# Schematic_transporter.net
KiCad netlist of a schematic drawn in EAGLE
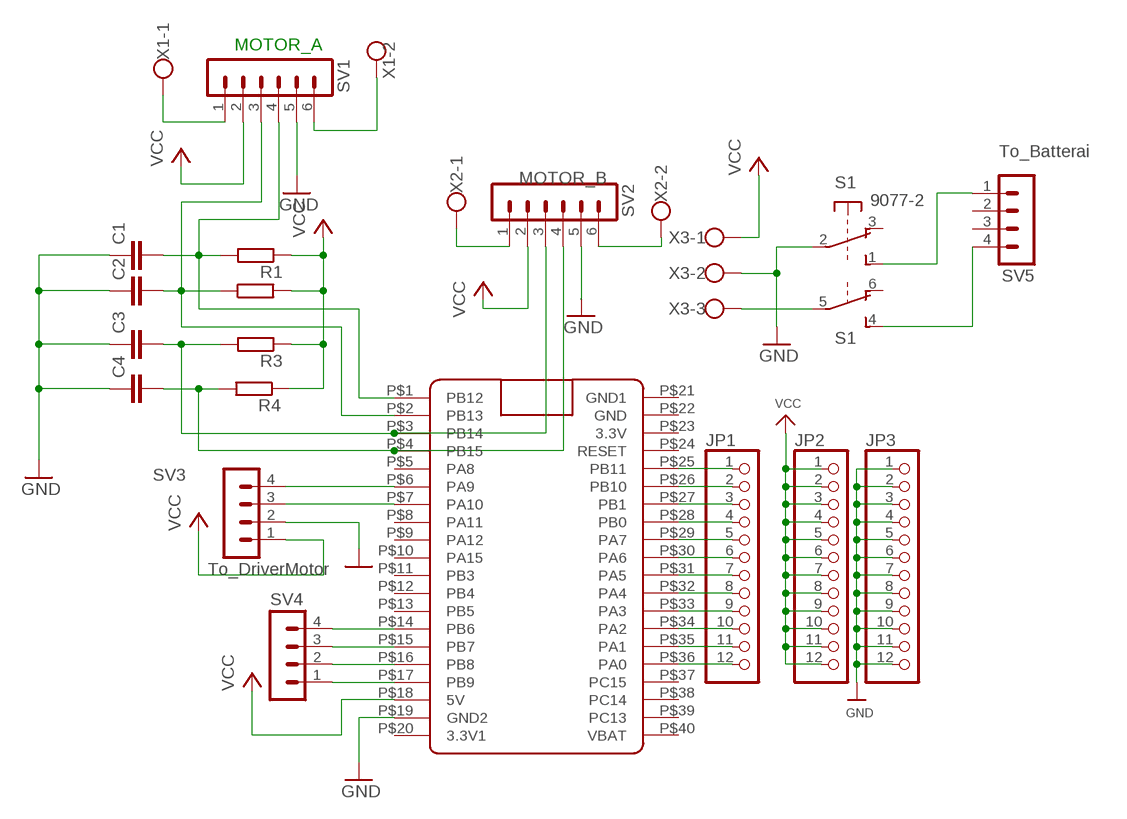
[diagram p0: schematic, sheet 1]

(export (version "E")
  (design (tool "Eeschema 10.0.6"))
  (components
    (comp (ref "C1")
      (value "C-EU050-024X044")
      (footprint "eagle-import:C050-024X044")
      (libsource (lib "eagle-import") (part "C-EU050-024X044"))
    )
    (comp (ref "C2")
      (value "C-EU050-024X044")
      (footprint "eagle-import:C050-024X044")
      (libsource (lib "eagle-import") (part "C-EU050-024X044"))
    )
    (comp (ref "C3")
      (value "C-EU050-024X044")
      (footprint "eagle-import:C050-024X044")
      (libsource (lib "eagle-import") (part "C-EU050-024X044"))
    )
    (comp (ref "C4")
      (value "C-EU050-024X044")
      (footprint "eagle-import:C050-024X044")
      (libsource (lib "eagle-import") (part "C-EU050-024X044"))
    )
    (comp (ref "JP1")
      (value "PINHD-1X12")
      (footprint "eagle-import:1X12")
      (libsource (lib "eagle-import") (part "PINHD-1X12"))
    )
    (comp (ref "JP2")
      (value "PINHD-1X12")
      (footprint "eagle-import:1X12")
      (libsource (lib "eagle-import") (part "PINHD-1X12"))
    )
    (comp (ref "JP3")
      (value "PINHD-1X12")
      (footprint "eagle-import:1X12")
      (libsource (lib "eagle-import") (part "PINHD-1X12"))
    )
    (comp (ref "R1")
      (value "R-EU_0207/7")
      (footprint "eagle-import:0207_7")
      (libsource (lib "eagle-import") (part "R-EU_0207/7"))
    )
    (comp (ref "R2")
      (value "R-EU_0207/7")
      (footprint "eagle-import:0207_7")
      (libsource (lib "eagle-import") (part "R-EU_0207/7"))
    )
    (comp (ref "R3")
      (value "R-EU_0207/7")
      (footprint "eagle-import:0207_7")
      (libsource (lib "eagle-import") (part "R-EU_0207/7"))
    )
    (comp (ref "R4")
      (value "R-EU_0207/7")
      (footprint "eagle-import:0207_7")
      (libsource (lib "eagle-import") (part "R-EU_0207/7"))
    )
    (comp (ref "S1")
      (value "9077-2")
      (footprint "eagle-import:9077-2")
      (libsource (lib "eagle-import") (part "9077-2"))
    )
    (comp (ref "SV1")
      (value "MA06-1")
      (footprint "eagle-import:MA06-1")
      (libsource (lib "eagle-import") (part "MA06-1"))
    )
    (comp (ref "SV2")
      (value "MA06-1")
      (footprint "eagle-import:MA06-1")
      (libsource (lib "eagle-import") (part "MA06-1"))
    )
    (comp (ref "SV3")
      (value "MA04-1")
      (footprint "eagle-import:MA04-1")
      (libsource (lib "eagle-import") (part "MA04-1"))
    )
    (comp (ref "SV4")
      (value "MA04-1")
      (footprint "eagle-import:MA04-1")
      (libsource (lib "eagle-import") (part "MA04-1"))
    )
    (comp (ref "SV5")
      (value "MA04-1")
      (footprint "eagle-import:MA04-1")
      (libsource (lib "eagle-import") (part "MA04-1"))
    )
    (comp (ref "U$1")
      (value "BLUE_PILL")
      (footprint "eagle-import:BLUE_PILL")
      (libsource (lib "eagle-import") (part "BLUE_PILL"))
    )
    (comp (ref "X1")
      (value "W237-102")
      (footprint "eagle-import:W237-102")
      (fields (field (name "MPN") "237-102"))
      (libsource (lib "eagle-import") (part "W237-102"))
    )
    (comp (ref "X2")
      (value "W237-102")
      (footprint "eagle-import:W237-102")
      (fields (field (name "MPN") "237-102"))
      (libsource (lib "eagle-import") (part "W237-102"))
    )
    (comp (ref "X3")
      (value "W237-103")
      (footprint "eagle-import:W237-103")
      (fields (field (name "MPN") "237-103"))
      (libsource (lib "eagle-import") (part "W237-103"))
    )
  )
  (nets
    (net (code "1") (name "/GND1") (class "Default")
      (node (ref "U$1") (pin "P$21") (pinfunction "GND1_P$21") (pintype "power_in"))
    )
    (net (code "2") (name "GND") (class "Default")
      (node (ref "C1") (pin "1") (pinfunction "1_1") (pintype "passive"))
      (node (ref "C2") (pin "1") (pinfunction "1_1") (pintype "passive"))
      (node (ref "C3") (pin "1") (pinfunction "1_1") (pintype "passive"))
      (node (ref "C4") (pin "1") (pinfunction "1_1") (pintype "passive"))
      (node (ref "JP3") (pin "1") (pinfunction "1_1") (pintype "passive"))
      (node (ref "JP3") (pin "10") (pinfunction "10_10") (pintype "passive"))
      (node (ref "JP3") (pin "11") (pinfunction "11_11") (pintype "passive"))
      (node (ref "JP3") (pin "12") (pinfunction "12_12") (pintype "passive"))
      (node (ref "JP3") (pin "2") (pinfunction "2_2") (pintype "passive"))
      (node (ref "JP3") (pin "3") (pinfunction "3_3") (pintype "passive"))
      (node (ref "JP3") (pin "4") (pinfunction "4_4") (pintype "passive"))
      (node (ref "JP3") (pin "5") (pinfunction "5_5") (pintype "passive"))
      (node (ref "JP3") (pin "6") (pinfunction "6_6") (pintype "passive"))
      (node (ref "JP3") (pin "7") (pinfunction "7_7") (pintype "passive"))
      (node (ref "JP3") (pin "8") (pinfunction "8_8") (pintype "passive"))
      (node (ref "JP3") (pin "9") (pinfunction "9_9") (pintype "passive"))
      (node (ref "S1") (pin "2") (pinfunction "P_2") (pintype "passive"))
      (node (ref "SV1") (pin "5") (pinfunction "5_5") (pintype "passive"))
      (node (ref "SV2") (pin "5") (pinfunction "5_5") (pintype "passive"))
      (node (ref "SV3") (pin "2") (pinfunction "2_2") (pintype "passive"))
      (node (ref "U$1") (pin "P$19") (pinfunction "GND2_P$19") (pintype "bidirectional"))
      (node (ref "X3") (pin "2") (pinfunction "KL_2") (pintype "passive"))
    )
    (net (code "3") (name "Net-(S1A-S)") (class "Default")
      (node (ref "S1") (pin "1") (pinfunction "S_1") (pintype "passive"))
      (node (ref "SV5") (pin "1") (pinfunction "1_1") (pintype "passive"))
    )
    (net (code "4") (name "Net-(S1B-P)") (class "Default")
      (node (ref "S1") (pin "5") (pinfunction "P_5") (pintype "passive"))
      (node (ref "X3") (pin "3") (pinfunction "KL_3") (pintype "passive"))
    )
    (net (code "5") (name "Net-(S1B-S)") (class "Default")
      (node (ref "S1") (pin "4") (pinfunction "S_4") (pintype "passive"))
      (node (ref "SV5") (pin "4") (pinfunction "4_4") (pintype "passive"))
    )
    (net (code "6") (name "Net-(U$1-PA0)") (class "Default")
      (node (ref "JP1") (pin "12") (pinfunction "12_12") (pintype "passive"))
      (node (ref "U$1") (pin "P$36") (pinfunction "PA0_P$36") (pintype "bidirectional"))
    )
    (net (code "7") (name "Net-(U$1-PA1)") (class "Default")
      (node (ref "JP1") (pin "11") (pinfunction "11_11") (pintype "passive"))
      (node (ref "U$1") (pin "P$35") (pinfunction "PA1_P$35") (pintype "bidirectional"))
    )
    (net (code "8") (name "Net-(U$1-PA2)") (class "Default")
      (node (ref "JP1") (pin "10") (pinfunction "10_10") (pintype "passive"))
      (node (ref "U$1") (pin "P$34") (pinfunction "PA2_P$34") (pintype "bidirectional"))
    )
    (net (code "9") (name "Net-(U$1-PA3)") (class "Default")
      (node (ref "JP1") (pin "9") (pinfunction "9_9") (pintype "passive"))
      (node (ref "U$1") (pin "P$33") (pinfunction "PA3_P$33") (pintype "bidirectional"))
    )
    (net (code "10") (name "Net-(U$1-PA4)") (class "Default")
      (node (ref "JP1") (pin "8") (pinfunction "8_8") (pintype "passive"))
      (node (ref "U$1") (pin "P$32") (pinfunction "PA4_P$32") (pintype "bidirectional"))
    )
    (net (code "11") (name "Net-(U$1-PA5)") (class "Default")
      (node (ref "JP1") (pin "7") (pinfunction "7_7") (pintype "passive"))
      (node (ref "U$1") (pin "P$31") (pinfunction "PA5_P$31") (pintype "bidirectional"))
    )
    (net (code "12") (name "Net-(U$1-PA6)") (class "Default")
      (node (ref "JP1") (pin "6") (pinfunction "6_6") (pintype "passive"))
      (node (ref "U$1") (pin "P$30") (pinfunction "PA6_P$30") (pintype "bidirectional"))
    )
    (net (code "13") (name "Net-(U$1-PA7)") (class "Default")
      (node (ref "JP1") (pin "5") (pinfunction "5_5") (pintype "passive"))
      (node (ref "U$1") (pin "P$29") (pinfunction "PA7_P$29") (pintype "bidirectional"))
    )
    (net (code "14") (name "Net-(U$1-PA9)") (class "Default")
      (node (ref "SV3") (pin "4") (pinfunction "4_4") (pintype "passive"))
      (node (ref "U$1") (pin "P$6") (pinfunction "PA9_P$6") (pintype "bidirectional"))
    )
    (net (code "15") (name "Net-(U$1-PA10)") (class "Default")
      (node (ref "SV3") (pin "3") (pinfunction "3_3") (pintype "passive"))
      (node (ref "U$1") (pin "P$7") (pinfunction "PA10_P$7") (pintype "bidirectional"))
    )
    (net (code "16") (name "Net-(U$1-PB0)") (class "Default")
      (node (ref "JP1") (pin "4") (pinfunction "4_4") (pintype "passive"))
      (node (ref "U$1") (pin "P$28") (pinfunction "PB0_P$28") (pintype "bidirectional"))
    )
    (net (code "17") (name "Net-(U$1-PB1)") (class "Default")
      (node (ref "JP1") (pin "3") (pinfunction "3_3") (pintype "passive"))
      (node (ref "U$1") (pin "P$27") (pinfunction "PB1_P$27") (pintype "bidirectional"))
    )
    (net (code "18") (name "Net-(U$1-PB6)") (class "Default")
      (node (ref "SV4") (pin "4") (pinfunction "4_4") (pintype "passive"))
      (node (ref "U$1") (pin "P$14") (pinfunction "PB6_P$14") (pintype "bidirectional"))
    )
    (net (code "19") (name "Net-(U$1-PB7)") (class "Default")
      (node (ref "SV4") (pin "3") (pinfunction "3_3") (pintype "passive"))
      (node (ref "U$1") (pin "P$15") (pinfunction "PB7_P$15") (pintype "bidirectional"))
    )
    (net (code "20") (name "Net-(U$1-PB8)") (class "Default")
      (node (ref "SV4") (pin "2") (pinfunction "2_2") (pintype "passive"))
      (node (ref "U$1") (pin "P$16") (pinfunction "PB8_P$16") (pintype "bidirectional"))
    )
    (net (code "21") (name "Net-(U$1-PB9)") (class "Default")
      (node (ref "SV4") (pin "1") (pinfunction "1_1") (pintype "passive"))
      (node (ref "U$1") (pin "P$17") (pinfunction "PB9_P$17") (pintype "bidirectional"))
    )
    (net (code "22") (name "Net-(U$1-PB10)") (class "Default")
      (node (ref "JP1") (pin "2") (pinfunction "2_2") (pintype "passive"))
      (node (ref "U$1") (pin "P$26") (pinfunction "PB10_P$26") (pintype "bidirectional"))
    )
    (net (code "23") (name "Net-(U$1-PB11)") (class "Default")
      (node (ref "JP1") (pin "1") (pinfunction "1_1") (pintype "passive"))
      (node (ref "U$1") (pin "P$25") (pinfunction "PB11_P$25") (pintype "bidirectional"))
    )
    (net (code "24") (name "Net-(U$1-PB12)") (class "Default")
      (node (ref "C1") (pin "2") (pinfunction "2_2") (pintype "passive"))
      (node (ref "R1") (pin "2") (pinfunction "2_2") (pintype "passive"))
      (node (ref "SV1") (pin "4") (pinfunction "4_4") (pintype "passive"))
      (node (ref "U$1") (pin "P$1") (pinfunction "PB12_P$1") (pintype "bidirectional"))
    )
    (net (code "25") (name "Net-(U$1-PB13)") (class "Default")
      (node (ref "C2") (pin "2") (pinfunction "2_2") (pintype "passive"))
      (node (ref "R2") (pin "1") (pinfunction "1_1") (pintype "passive"))
      (node (ref "SV1") (pin "3") (pinfunction "3_3") (pintype "passive"))
      (node (ref "U$1") (pin "P$2") (pinfunction "PB13_P$2") (pintype "bidirectional"))
    )
    (net (code "26") (name "Net-(U$1-PB14)") (class "Default")
      (node (ref "C3") (pin "2") (pinfunction "2_2") (pintype "passive"))
      (node (ref "R3") (pin "2") (pinfunction "2_2") (pintype "passive"))
      (node (ref "SV2") (pin "3") (pinfunction "3_3") (pintype "passive"))
      (node (ref "U$1") (pin "P$3") (pinfunction "PB14_P$3") (pintype "bidirectional"))
    )
    (net (code "27") (name "Net-(U$1-PB15)") (class "Default")
      (node (ref "C4") (pin "2") (pinfunction "2_2") (pintype "passive"))
      (node (ref "R4") (pin "2") (pinfunction "2_2") (pintype "passive"))
      (node (ref "SV2") (pin "4") (pinfunction "4_4") (pintype "passive"))
      (node (ref "U$1") (pin "P$4") (pinfunction "PB15_P$4") (pintype "bidirectional"))
    )
    (net (code "28") (name "Net-(X1A-KL)") (class "Default")
      (node (ref "SV1") (pin "1") (pinfunction "1_1") (pintype "passive"))
      (node (ref "X1") (pin "1") (pinfunction "KL_1") (pintype "passive"))
    )
    (net (code "29") (name "Net-(X1B-KL)") (class "Default")
      (node (ref "SV1") (pin "6") (pinfunction "6_6") (pintype "passive"))
      (node (ref "X1") (pin "2") (pinfunction "KL_2") (pintype "passive"))
    )
    (net (code "30") (name "Net-(X2A-KL)") (class "Default")
      (node (ref "SV2") (pin "1") (pinfunction "1_1") (pintype "passive"))
      (node (ref "X2") (pin "1") (pinfunction "KL_1") (pintype "passive"))
    )
    (net (code "31") (name "Net-(X2B-KL)") (class "Default")
      (node (ref "SV2") (pin "6") (pinfunction "6_6") (pintype "passive"))
      (node (ref "X2") (pin "2") (pinfunction "KL_2") (pintype "passive"))
    )
    (net (code "32") (name "VCC") (class "Default")
      (node (ref "JP2") (pin "1") (pinfunction "1_1") (pintype "passive"))
      (node (ref "JP2") (pin "10") (pinfunction "10_10") (pintype "passive"))
      (node (ref "JP2") (pin "11") (pinfunction "11_11") (pintype "passive"))
      (node (ref "JP2") (pin "12") (pinfunction "12_12") (pintype "passive"))
      (node (ref "JP2") (pin "2") (pinfunction "2_2") (pintype "passive"))
      (node (ref "JP2") (pin "3") (pinfunction "3_3") (pintype "passive"))
      (node (ref "JP2") (pin "4") (pinfunction "4_4") (pintype "passive"))
      (node (ref "JP2") (pin "5") (pinfunction "5_5") (pintype "passive"))
      (node (ref "JP2") (pin "6") (pinfunction "6_6") (pintype "passive"))
      (node (ref "JP2") (pin "7") (pinfunction "7_7") (pintype "passive"))
      (node (ref "JP2") (pin "8") (pinfunction "8_8") (pintype "passive"))
      (node (ref "JP2") (pin "9") (pinfunction "9_9") (pintype "passive"))
      (node (ref "R1") (pin "1") (pinfunction "1_1") (pintype "passive"))
      (node (ref "R2") (pin "2") (pinfunction "2_2") (pintype "passive"))
      (node (ref "R3") (pin "1") (pinfunction "1_1") (pintype "passive"))
      (node (ref "R4") (pin "1") (pinfunction "1_1") (pintype "passive"))
      (node (ref "SV1") (pin "2") (pinfunction "2_2") (pintype "passive"))
      (node (ref "SV2") (pin "2") (pinfunction "2_2") (pintype "passive"))
      (node (ref "SV3") (pin "1") (pinfunction "1_1") (pintype "passive"))
      (node (ref "U$1") (pin "P$18") (pinfunction "5V_P$18") (pintype "bidirectional"))
      (node (ref "X3") (pin "1") (pinfunction "KL_1") (pintype "passive"))
    )
    (net (code "33") (name "unconnected-(S1A-O-Pad3)") (class "Default")
      (node (ref "S1") (pin "3") (pinfunction "O_3") (pintype "passive"))
    )
    (net (code "34") (name "unconnected-(S1B-O-Pad6)") (class "Default")
      (node (ref "S1") (pin "6") (pinfunction "O_6") (pintype "passive"))
    )
    (net (code "35") (name "unconnected-(SV5-Pad2)") (class "Default")
      (node (ref "SV5") (pin "2") (pinfunction "2_2") (pintype "passive"))
    )
    (net (code "36") (name "unconnected-(SV5-Pad3)") (class "Default")
      (node (ref "SV5") (pin "3") (pinfunction "3_3") (pintype "passive"))
    )
    (net (code "37") (name "unconnected-(U$1-3.3V-PadP$23)") (class "Default")
      (node (ref "U$1") (pin "P$23") (pinfunction "3.3V_P$23") (pintype "bidirectional"))
    )
    (net (code "38") (name "unconnected-(U$1-3.3V1-PadP$20)") (class "Default")
      (node (ref "U$1") (pin "P$20") (pinfunction "3.3V1_P$20") (pintype "bidirectional"))
    )
    (net (code "39") (name "unconnected-(U$1-GND-PadP$22)") (class "Default")
      (node (ref "U$1") (pin "P$22") (pinfunction "GND_P$22") (pintype "bidirectional"))
    )
    (net (code "40") (name "unconnected-(U$1-PA8-PadP$5)") (class "Default")
      (node (ref "U$1") (pin "P$5") (pinfunction "PA8_P$5") (pintype "bidirectional"))
    )
    (net (code "41") (name "unconnected-(U$1-PA11-PadP$8)") (class "Default")
      (node (ref "U$1") (pin "P$8") (pinfunction "PA11_P$8") (pintype "bidirectional"))
    )
    (net (code "42") (name "unconnected-(U$1-PA12-PadP$9)") (class "Default")
      (node (ref "U$1") (pin "P$9") (pinfunction "PA12_P$9") (pintype "bidirectional"))
    )
    (net (code "43") (name "unconnected-(U$1-PA15-PadP$10)") (class "Default")
      (node (ref "U$1") (pin "P$10") (pinfunction "PA15_P$10") (pintype "bidirectional"))
    )
    (net (code "44") (name "unconnected-(U$1-PB3-PadP$11)") (class "Default")
      (node (ref "U$1") (pin "P$11") (pinfunction "PB3_P$11") (pintype "bidirectional"))
    )
    (net (code "45") (name "unconnected-(U$1-PB4-PadP$12)") (class "Default")
      (node (ref "U$1") (pin "P$12") (pinfunction "PB4_P$12") (pintype "bidirectional"))
    )
    (net (code "46") (name "unconnected-(U$1-PB5-PadP$13)") (class "Default")
      (node (ref "U$1") (pin "P$13") (pinfunction "PB5_P$13") (pintype "bidirectional"))
    )
    (net (code "47") (name "unconnected-(U$1-PC13-PadP$39)") (class "Default")
      (node (ref "U$1") (pin "P$39") (pinfunction "PC13_P$39") (pintype "bidirectional"))
    )
    (net (code "48") (name "unconnected-(U$1-PC14-PadP$38)") (class "Default")
      (node (ref "U$1") (pin "P$38") (pinfunction "PC14_P$38") (pintype "bidirectional"))
    )
    (net (code "49") (name "unconnected-(U$1-PC15-PadP$37)") (class "Default")
      (node (ref "U$1") (pin "P$37") (pinfunction "PC15_P$37") (pintype "bidirectional"))
    )
    (net (code "50") (name "unconnected-(U$1-RESET-PadP$24)") (class "Default")
      (node (ref "U$1") (pin "P$24") (pinfunction "RESET_P$24") (pintype "bidirectional"))
    )
    (net (code "51") (name "unconnected-(U$1-VBAT-PadP$40)") (class "Default")
      (node (ref "U$1") (pin "P$40") (pinfunction "VBAT_P$40") (pintype "bidirectional"))
    )
  )
)
